# Forest-Joystick-Mouse-Hub.net
KiCad netlist of a schematic drawn in EAGLE
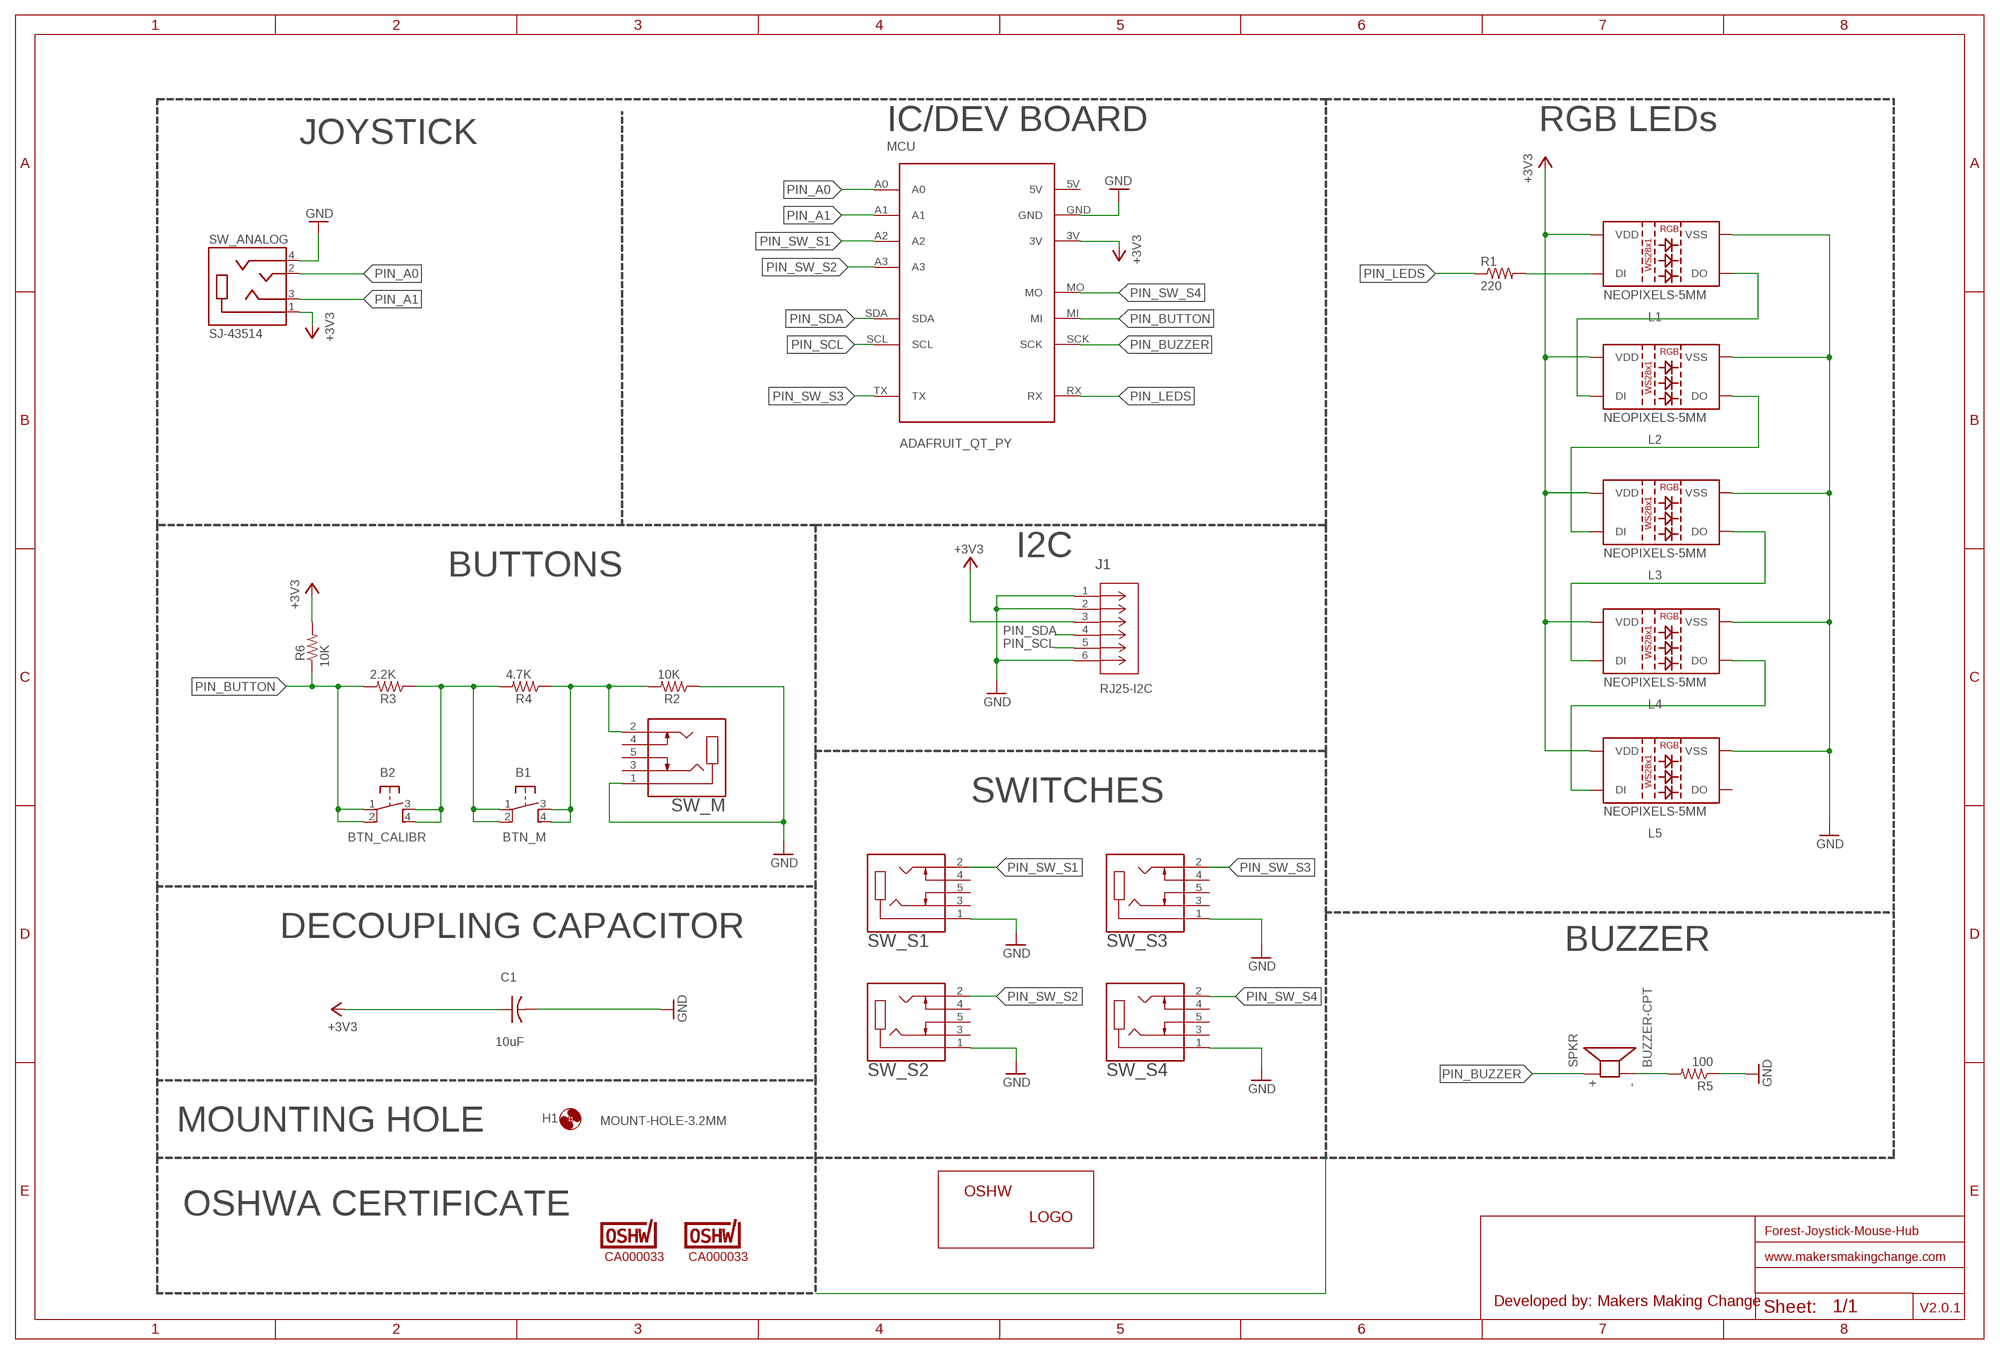
[diagram p0: schematic, sheet 1]

(export (version "E")
  (design (tool "Eeschema 10.0.6"))
  (components
    (comp (ref "B1")
      (value "BTN_M")
      (footprint "eagle-import:B3F-5050")
      (libsource (lib "eagle-import") (part "SWITCH_OMRON-PTH-12"))
    )
    (comp (ref "B2")
      (value "BTN_CALIBR")
      (footprint "eagle-import:B3F-5050")
      (libsource (lib "eagle-import") (part "SWITCH_OMRON-PTH-12"))
    )
    (comp (ref "C1")
      (value "10uF")
      (footprint "eagle-import:CAP-050-030X075")
      (libsource (lib "eagle-import") (part "CAPACITOR-US-050-030X075"))
    )
    (comp (ref "H1")
      (value "MOUNT-HOLE-3.2MM")
      (footprint "eagle-import:HOLE-3.2MM")
      (libsource (lib "eagle-import") (part "MOUNT-HOLE-3.2MM"))
    )
    (comp (ref "J1")
      (value "5555165-1")
      (footprint "eagle-import:CONN6_5555165-1")
      (fields
        (field (name "LABEL") "RJ25-I2C")
        (field (name "COPYRIGHT") "Copyright (C) 2023 Ultra Librarian. All rights reserved.")
      )
      (libsource (lib "eagle-import") (part "5555165-1"))
    )
    (comp (ref "L1")
      (value "NEOPIXELS-5MM")
      (footprint "eagle-import:NEOPIXELS-5MM")
      (libsource (lib "eagle-import") (part "NEOPIXELS-5MM"))
    )
    (comp (ref "L2")
      (value "NEOPIXELS-5MM")
      (footprint "eagle-import:NEOPIXELS-5MM")
      (libsource (lib "eagle-import") (part "NEOPIXELS-5MM"))
    )
    (comp (ref "L3")
      (value "NEOPIXELS-5MM")
      (footprint "eagle-import:NEOPIXELS-5MM")
      (libsource (lib "eagle-import") (part "NEOPIXELS-5MM"))
    )
    (comp (ref "L4")
      (value "NEOPIXELS-5MM")
      (footprint "eagle-import:NEOPIXELS-5MM")
      (libsource (lib "eagle-import") (part "NEOPIXELS-5MM"))
    )
    (comp (ref "L5")
      (value "NEOPIXELS-5MM")
      (footprint "eagle-import:NEOPIXELS-5MM")
      (libsource (lib "eagle-import") (part "NEOPIXELS-5MM"))
    )
    (comp (ref "LOGO-OSHWA")
      (value "CA000033")
      (footprint "eagle-import:OSHWA-CERT-SMALL-SILK")
      (libsource (lib "eagle-import") (part "OSHWA-LOGO-SMALL"))
    )
    (comp (ref "MCU")
      (value "ADAFRUIT_QT_PY")
      (footprint "eagle-import:QT_PY")
      (libsource (lib "eagle-import") (part "ADAFRUIT_QT_PY"))
    )
    (comp (ref "R1")
      (value "220")
      (footprint "eagle-import:RESISTOR_0206_8")
      (libsource (lib "eagle-import") (part "RESISTOR-US-0206/8"))
    )
    (comp (ref "R2")
      (value "10K")
      (footprint "eagle-import:RESISTOR_0206_8")
      (libsource (lib "eagle-import") (part "RESISTOR-US-0206/8"))
    )
    (comp (ref "R3")
      (value "2.2K")
      (footprint "eagle-import:RESISTOR_0206_8")
      (libsource (lib "eagle-import") (part "RESISTOR-US-0206/8"))
    )
    (comp (ref "R4")
      (value "4.7K")
      (footprint "eagle-import:RESISTOR_0206_8")
      (libsource (lib "eagle-import") (part "RESISTOR-US-0206/8"))
    )
    (comp (ref "R5")
      (value "100")
      (footprint "eagle-import:RESISTOR_0206_8")
      (libsource (lib "eagle-import") (part "RESISTOR-US-0206/8"))
    )
    (comp (ref "R6")
      (value "10K")
      (footprint "eagle-import:RESISTOR_0206_8")
      (libsource (lib "eagle-import") (part "RESISTOR-US-0206/8"))
    )
    (comp (ref "SPKR")
      (value "BUZZER-CPT")
      (footprint "eagle-import:CUI_CPT-1255C-090")
      (libsource (lib "eagle-import") (part "BUZZER-CPT"))
    )
    (comp (ref "SW_ANALOG")
      (value "SJ-43514")
      (footprint "eagle-import:CUI_SJ-43514")
      (libsource (lib "eagle-import") (part "SJ-43514"))
    )
    (comp (ref "SW_M")
      (value "CUI_SJ1-3535NGSJ1-3535NG")
      (footprint "eagle-import:CUI_SJ1-3535NG")
      (libsource (lib "eagle-import") (part "CUI_SJ1-3535NGSJ1-3535NG"))
    )
    (comp (ref "SW_S1")
      (value "CUI_SJ1-3535NGSJ1-3535NG")
      (footprint "eagle-import:CUI_SJ1-3535NG")
      (libsource (lib "eagle-import") (part "CUI_SJ1-3535NGSJ1-3535NG"))
    )
    (comp (ref "SW_S2")
      (value "CUI_SJ1-3535NGSJ1-3535NG")
      (footprint "eagle-import:CUI_SJ1-3535NG")
      (libsource (lib "eagle-import") (part "CUI_SJ1-3535NGSJ1-3535NG"))
    )
    (comp (ref "SW_S3")
      (value "CUI_SJ1-3535NGSJ1-3535NG")
      (footprint "eagle-import:CUI_SJ1-3535NG")
      (libsource (lib "eagle-import") (part "CUI_SJ1-3535NGSJ1-3535NG"))
    )
    (comp (ref "SW_S4")
      (value "CUI_SJ1-3535NGSJ1-3535NG")
      (footprint "eagle-import:CUI_SJ1-3535NG")
      (libsource (lib "eagle-import") (part "CUI_SJ1-3535NGSJ1-3535NG"))
    )
    (comp (ref "U$3")
      (value "OSHW_LOGO-XSM")
      (footprint "eagle-import:OSHW_X-SMALL_LOGO")
      (libsource (lib "eagle-import") (part "OSHW_LOGO-XSM"))
    )
    (comp (ref "U$4")
      (value "CA000033")
      (footprint "eagle-import:OSHWA-CERT-SMALL-SILK")
      (libsource (lib "eagle-import") (part "OSHWA-LOGO-SMALL"))
    )
  )
  (nets
    (net (code "1") (name "+3V3") (class "Default")
      (node (ref "C1") (pin "1") (pinfunction "1_1") (pintype "passive"))
      (node (ref "J1") (pin "3") (pinfunction "3_3") (pintype "passive"))
      (node (ref "L1") (pin "P2") (pinfunction "VDD_P2") (pintype "bidirectional"))
      (node (ref "L2") (pin "P2") (pinfunction "VDD_P2") (pintype "bidirectional"))
      (node (ref "L3") (pin "P2") (pinfunction "VDD_P2") (pintype "bidirectional"))
      (node (ref "L4") (pin "P2") (pinfunction "VDD_P2") (pintype "bidirectional"))
      (node (ref "L5") (pin "P2") (pinfunction "VDD_P2") (pintype "bidirectional"))
      (node (ref "MCU") (pin "3V") (pinfunction "3V_3V") (pintype "bidirectional"))
      (node (ref "R6") (pin "2") (pinfunction "2_2") (pintype "passive"))
      (node (ref "SW_ANALOG") (pin "1") (pinfunction "SLEEVE_1") (pintype "passive"))
    )
    (net (code "2") (name "GND") (class "Default")
      (node (ref "C1") (pin "2") (pinfunction "2_2") (pintype "passive"))
      (node (ref "J1") (pin "1") (pinfunction "1_1") (pintype "passive"))
      (node (ref "J1") (pin "2") (pinfunction "2_2") (pintype "passive"))
      (node (ref "J1") (pin "6") (pinfunction "6_6") (pintype "passive"))
      (node (ref "L1") (pin "P3") (pinfunction "VSS_P3") (pintype "bidirectional"))
      (node (ref "L2") (pin "P3") (pinfunction "VSS_P3") (pintype "bidirectional"))
      (node (ref "L3") (pin "P3") (pinfunction "VSS_P3") (pintype "bidirectional"))
      (node (ref "L4") (pin "P3") (pinfunction "VSS_P3") (pintype "bidirectional"))
      (node (ref "L5") (pin "P3") (pinfunction "VSS_P3") (pintype "bidirectional"))
      (node (ref "MCU") (pin "GND") (pinfunction "GND_GND") (pintype "bidirectional"))
      (node (ref "R2") (pin "1") (pinfunction "1_1") (pintype "passive"))
      (node (ref "R5") (pin "1") (pinfunction "1_1") (pintype "passive"))
      (node (ref "SW_ANALOG") (pin "4") (pinfunction "RING2_4") (pintype "passive"))
      (node (ref "SW_M") (pin "1") (pinfunction "1_1") (pintype "passive"))
      (node (ref "SW_S1") (pin "1") (pinfunction "1_1") (pintype "passive"))
      (node (ref "SW_S2") (pin "1") (pinfunction "1_1") (pintype "passive"))
      (node (ref "SW_S3") (pin "1") (pinfunction "1_1") (pintype "passive"))
      (node (ref "SW_S4") (pin "1") (pinfunction "1_1") (pintype "passive"))
    )
    (net (code "3") (name "Net-(B1-Pad1)") (class "Default")
      (node (ref "B1") (pin "1") (pinfunction "1_1") (pintype "passive"))
      (node (ref "B1") (pin "2") (pinfunction "2_2") (pintype "passive"))
      (node (ref "B2") (pin "3") (pinfunction "3_3") (pintype "passive"))
      (node (ref "B2") (pin "4") (pinfunction "4_4") (pintype "passive"))
      (node (ref "R3") (pin "1") (pinfunction "1_1") (pintype "passive"))
      (node (ref "R4") (pin "2") (pinfunction "2_2") (pintype "passive"))
    )
    (net (code "4") (name "Net-(B1-Pad3)") (class "Default")
      (node (ref "B1") (pin "3") (pinfunction "3_3") (pintype "passive"))
      (node (ref "B1") (pin "4") (pinfunction "4_4") (pintype "passive"))
      (node (ref "R2") (pin "2") (pinfunction "2_2") (pintype "passive"))
      (node (ref "R4") (pin "1") (pinfunction "1_1") (pintype "passive"))
      (node (ref "SW_M") (pin "2") (pinfunction "2_2") (pintype "passive"))
    )
    (net (code "5") (name "Net-(L1-DI)") (class "Default")
      (node (ref "L1") (pin "P1") (pinfunction "DI_P1") (pintype "bidirectional"))
      (node (ref "R1") (pin "2") (pinfunction "2_2") (pintype "passive"))
    )
    (net (code "6") (name "Net-(L1-DO)") (class "Default")
      (node (ref "L1") (pin "P4") (pinfunction "DO_P4") (pintype "bidirectional"))
      (node (ref "L2") (pin "P1") (pinfunction "DI_P1") (pintype "bidirectional"))
    )
    (net (code "7") (name "Net-(L2-DO)") (class "Default")
      (node (ref "L2") (pin "P4") (pinfunction "DO_P4") (pintype "bidirectional"))
      (node (ref "L3") (pin "P1") (pinfunction "DI_P1") (pintype "bidirectional"))
    )
    (net (code "8") (name "Net-(L3-DO)") (class "Default")
      (node (ref "L3") (pin "P4") (pinfunction "DO_P4") (pintype "bidirectional"))
      (node (ref "L4") (pin "P1") (pinfunction "DI_P1") (pintype "bidirectional"))
    )
    (net (code "9") (name "Net-(L4-DO)") (class "Default")
      (node (ref "L4") (pin "P4") (pinfunction "DO_P4") (pintype "bidirectional"))
      (node (ref "L5") (pin "P1") (pinfunction "DI_P1") (pintype "bidirectional"))
    )
    (net (code "10") (name "Net-(R5-Pad2)") (class "Default")
      (node (ref "R5") (pin "2") (pinfunction "2_2") (pintype "passive"))
      (node (ref "SPKR") (pin "N") (pinfunction "N_N") (pintype "passive"))
    )
    (net (code "11") (name "PIN_A0") (class "Default")
      (node (ref "MCU") (pin "A0") (pinfunction "A0_A0") (pintype "bidirectional"))
      (node (ref "SW_ANALOG") (pin "2") (pinfunction "TIP_2") (pintype "passive"))
    )
    (net (code "12") (name "PIN_A1") (class "Default")
      (node (ref "MCU") (pin "A1") (pinfunction "A1_A1") (pintype "bidirectional"))
      (node (ref "SW_ANALOG") (pin "3") (pinfunction "RING1_3") (pintype "passive"))
    )
    (net (code "13") (name "PIN_BUTTON") (class "Default")
      (node (ref "B2") (pin "1") (pinfunction "1_1") (pintype "passive"))
      (node (ref "B2") (pin "2") (pinfunction "2_2") (pintype "passive"))
      (node (ref "MCU") (pin "MI") (pinfunction "MI_MI") (pintype "bidirectional"))
      (node (ref "R3") (pin "2") (pinfunction "2_2") (pintype "passive"))
      (node (ref "R6") (pin "1") (pinfunction "1_1") (pintype "passive"))
    )
    (net (code "14") (name "PIN_BUZZER") (class "Default")
      (node (ref "MCU") (pin "SCK") (pinfunction "SCK_SCK") (pintype "bidirectional"))
      (node (ref "SPKR") (pin "P") (pinfunction "P_P") (pintype "passive"))
    )
    (net (code "15") (name "PIN_LEDS") (class "Default")
      (node (ref "MCU") (pin "RX") (pinfunction "RX_RX") (pintype "bidirectional"))
      (node (ref "R1") (pin "1") (pinfunction "1_1") (pintype "passive"))
    )
    (net (code "16") (name "PIN_SCL") (class "Default")
      (node (ref "J1") (pin "5") (pinfunction "5_5") (pintype "passive"))
      (node (ref "MCU") (pin "SCL") (pinfunction "SCL_SCL") (pintype "bidirectional"))
    )
    (net (code "17") (name "PIN_SDA") (class "Default")
      (node (ref "J1") (pin "4") (pinfunction "4_4") (pintype "passive"))
      (node (ref "MCU") (pin "SDA") (pinfunction "SDA_SDA") (pintype "bidirectional"))
    )
    (net (code "18") (name "PIN_SW_S1") (class "Default")
      (node (ref "MCU") (pin "A2") (pinfunction "A2_A2") (pintype "bidirectional"))
      (node (ref "SW_S1") (pin "2") (pinfunction "2_2") (pintype "passive"))
    )
    (net (code "19") (name "PIN_SW_S2") (class "Default")
      (node (ref "MCU") (pin "A3") (pinfunction "A3_A3") (pintype "bidirectional"))
      (node (ref "SW_S2") (pin "2") (pinfunction "2_2") (pintype "passive"))
    )
    (net (code "20") (name "PIN_SW_S3") (class "Default")
      (node (ref "MCU") (pin "TX") (pinfunction "TX_TX") (pintype "bidirectional"))
      (node (ref "SW_S3") (pin "2") (pinfunction "2_2") (pintype "passive"))
    )
    (net (code "21") (name "PIN_SW_S4") (class "Default")
      (node (ref "MCU") (pin "MO") (pinfunction "MO_MO") (pintype "bidirectional"))
      (node (ref "SW_S4") (pin "2") (pinfunction "2_2") (pintype "passive"))
    )
    (net (code "22") (name "unconnected-(L5-DO-PadP4)") (class "Default")
      (node (ref "L5") (pin "P4") (pinfunction "DO_P4") (pintype "bidirectional"))
    )
    (net (code "23") (name "unconnected-(MCU-Pad5V)") (class "Default")
      (node (ref "MCU") (pin "5V") (pinfunction "5V_5V") (pintype "bidirectional"))
    )
    (net (code "24") (name "unconnected-(SW_M-Pad3)") (class "Default")
      (node (ref "SW_M") (pin "3") (pinfunction "3_3") (pintype "passive"))
    )
    (net (code "25") (name "unconnected-(SW_M-Pad4)") (class "Default")
      (node (ref "SW_M") (pin "4") (pinfunction "4_4") (pintype "passive"))
    )
    (net (code "26") (name "unconnected-(SW_M-Pad5)") (class "Default")
      (node (ref "SW_M") (pin "5") (pinfunction "5_5") (pintype "passive"))
    )
    (net (code "27") (name "unconnected-(SW_S1-Pad3)") (class "Default")
      (node (ref "SW_S1") (pin "3") (pinfunction "3_3") (pintype "passive"))
    )
    (net (code "28") (name "unconnected-(SW_S1-Pad4)") (class "Default")
      (node (ref "SW_S1") (pin "4") (pinfunction "4_4") (pintype "passive"))
    )
    (net (code "29") (name "unconnected-(SW_S1-Pad5)") (class "Default")
      (node (ref "SW_S1") (pin "5") (pinfunction "5_5") (pintype "passive"))
    )
    (net (code "30") (name "unconnected-(SW_S2-Pad3)") (class "Default")
      (node (ref "SW_S2") (pin "3") (pinfunction "3_3") (pintype "passive"))
    )
    (net (code "31") (name "unconnected-(SW_S2-Pad4)") (class "Default")
      (node (ref "SW_S2") (pin "4") (pinfunction "4_4") (pintype "passive"))
    )
    (net (code "32") (name "unconnected-(SW_S2-Pad5)") (class "Default")
      (node (ref "SW_S2") (pin "5") (pinfunction "5_5") (pintype "passive"))
    )
    (net (code "33") (name "unconnected-(SW_S3-Pad3)") (class "Default")
      (node (ref "SW_S3") (pin "3") (pinfunction "3_3") (pintype "passive"))
    )
    (net (code "34") (name "unconnected-(SW_S3-Pad4)") (class "Default")
      (node (ref "SW_S3") (pin "4") (pinfunction "4_4") (pintype "passive"))
    )
    (net (code "35") (name "unconnected-(SW_S3-Pad5)") (class "Default")
      (node (ref "SW_S3") (pin "5") (pinfunction "5_5") (pintype "passive"))
    )
    (net (code "36") (name "unconnected-(SW_S4-Pad3)") (class "Default")
      (node (ref "SW_S4") (pin "3") (pinfunction "3_3") (pintype "passive"))
    )
    (net (code "37") (name "unconnected-(SW_S4-Pad4)") (class "Default")
      (node (ref "SW_S4") (pin "4") (pinfunction "4_4") (pintype "passive"))
    )
    (net (code "38") (name "unconnected-(SW_S4-Pad5)") (class "Default")
      (node (ref "SW_S4") (pin "5") (pinfunction "5_5") (pintype "passive"))
    )
  )
)
